# 05_Audio.net
KiCad netlist of a schematic drawn in Altium Designer
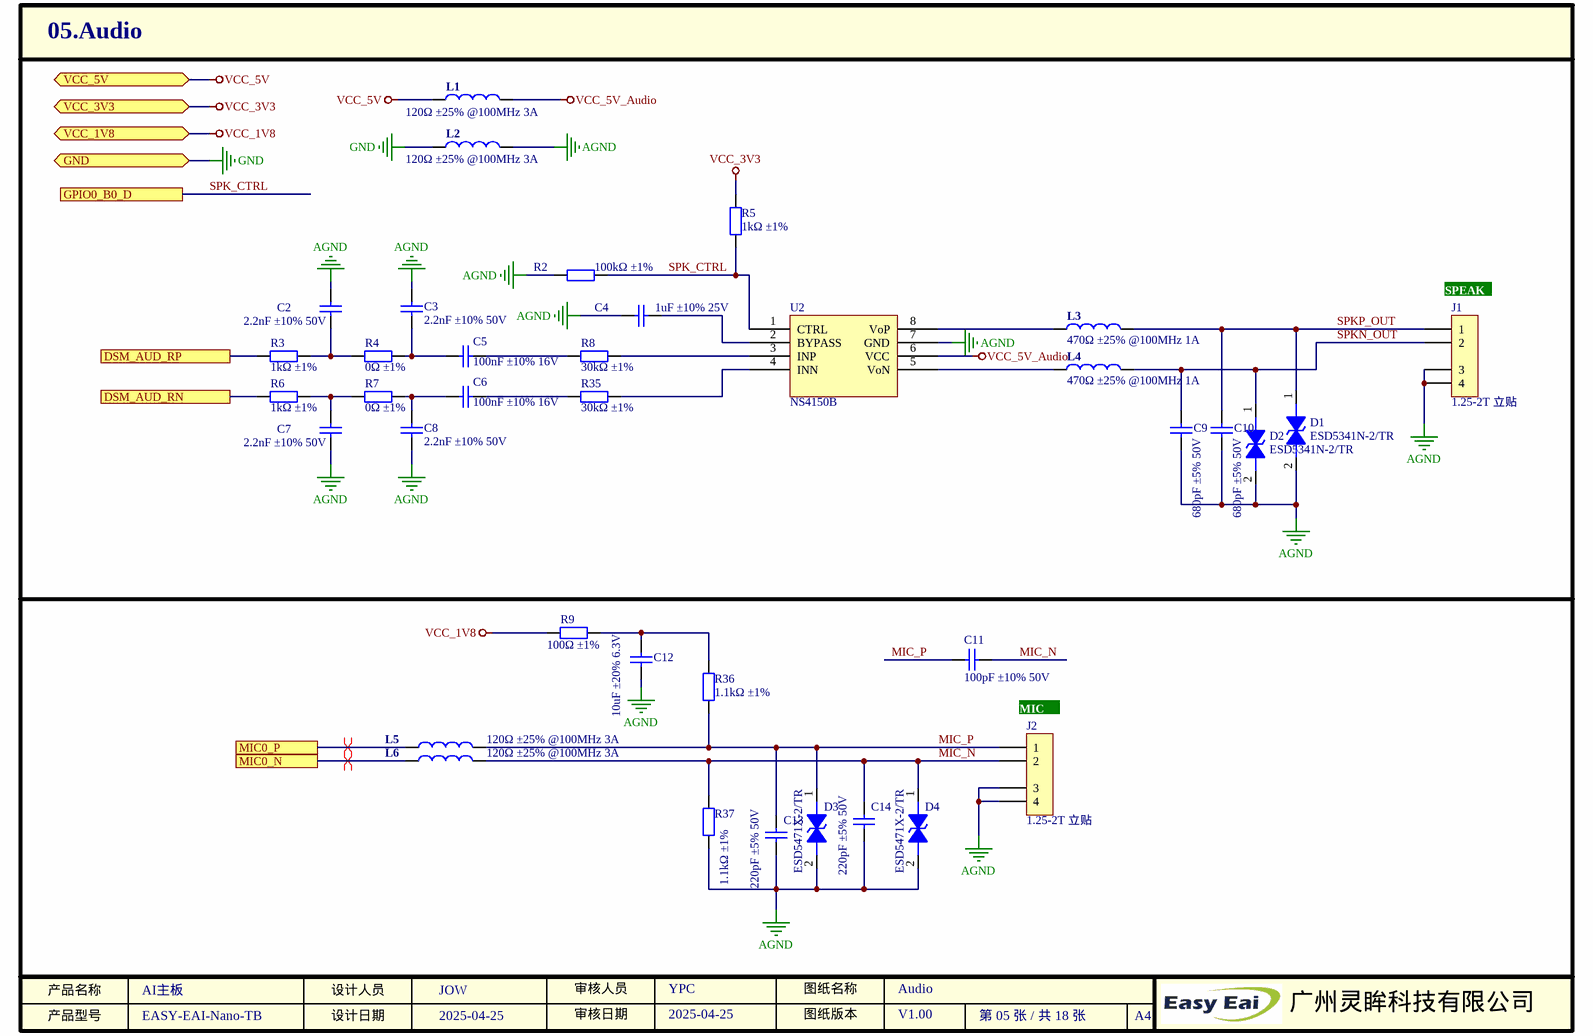
[diagram p0: 05.Audio.SchDoc]

(export (version "E")
  (design (tool "Eeschema 10.0.6"))
  (components
    (comp (ref "C2")
      (value "0402B222K500NT")
      (footprint "0402_C")
      (description "SPZL000399")
      (fields (field (name "描述") "2.2nF ±10% 50V"))
      (libsource (lib "CAP_EASY-EAI") (part "0402 2.2nF ±10% 50V"))
    )
    (comp (ref "C3")
      (value "0402B222K500NT")
      (footprint "0402_C")
      (description "SPZL000399")
      (fields (field (name "描述") "2.2nF ±10% 50V"))
      (libsource (lib "CAP_EASY-EAI") (part "0402 2.2nF ±10% 50V"))
    )
    (comp (ref "C4")
      (value "CL05A105KA5NQNC")
      (footprint "0402_C")
      (description "SPZL000337")
      (fields (field (name "描述") "1uF ±10% 25V"))
      (libsource (lib "CAP_EASY-EAI") (part "0402 1uF ±10% 25V"))
    )
    (comp (ref "C5")
      (value "CL05B104KO5NNNC")
      (footprint "0402_C")
      (description "SPZL000259")
      (fields (field (name "描述") "100nF ±10% 16V"))
      (libsource (lib "CAP_EASY-EAI") (part "0402 100nF ±10% 16V"))
    )
    (comp (ref "C6")
      (value "CL05B104KO5NNNC")
      (footprint "0402_C")
      (description "SPZL000259")
      (fields (field (name "描述") "100nF ±10% 16V"))
      (libsource (lib "CAP_EASY-EAI") (part "0402 100nF ±10% 16V"))
    )
    (comp (ref "C7")
      (value "0402B222K500NT")
      (footprint "0402_C")
      (description "SPZL000399")
      (fields (field (name "描述") "2.2nF ±10% 50V"))
      (libsource (lib "CAP_EASY-EAI") (part "0402 2.2nF ±10% 50V"))
    )
    (comp (ref "C8")
      (value "0402B222K500NT")
      (footprint "0402_C")
      (description "SPZL000399")
      (fields (field (name "描述") "2.2nF ±10% 50V"))
      (libsource (lib "CAP_EASY-EAI") (part "0402 2.2nF ±10% 50V"))
    )
    (comp (ref "C9")
      (value "CL05C681JB5NNNC")
      (footprint "0402_C")
      (description "SPZL000317")
      (fields (field (name "描述") "680pF ±5% 50V"))
      (libsource (lib "CAP_EASY-EAI") (part "0402 680pF ±5% 50V"))
    )
    (comp (ref "C10")
      (value "CL05C681JB5NNNC")
      (footprint "0402_C")
      (description "SPZL000317")
      (fields (field (name "描述") "680pF ±5% 50V"))
      (libsource (lib "CAP_EASY-EAI") (part "0402 680pF ±5% 50V"))
    )
    (comp (ref "C11")
      (value "CC0402KRX7R9BB101")
      (footprint "0402_C")
      (description "SPZL000312")
      (fields (field (name "描述") "100pF ±10% 50V"))
      (libsource (lib "CAP_EASY-EAI") (part "0402 100pF ±10% 50V"))
    )
    (comp (ref "C12")
      (value "CL05A106MQ5NUNC")
      (footprint "0402_C")
      (description "SPZL000269")
      (fields (field (name "描述") "10uF ±20% 6.3V"))
      (libsource (lib "CAP_lexing") (part "0402 10uF ±20% 6.3V"))
    )
    (comp (ref "C13")
      (value "GCM1555G1H221JA16D")
      (footprint "0402_C")
      (description "SPZL000318")
      (fields (field (name "描述") "220pF ±5% 50V"))
      (libsource (lib "CAP_lexing") (part "0402 220pF ±5% 50V"))
    )
    (comp (ref "C14")
      (value "GCM1555G1H221JA16D")
      (footprint "0402_C")
      (description "SPZL000318")
      (fields (field (name "描述") "220pF ±5% 50V"))
      (libsource (lib "CAP_lexing") (part "0402 220pF ±5% 50V"))
    )
    (comp (ref "D1")
      (value "ESD5341N-2/TR")
      (footprint "DFN1006-2L")
      (description "SPZL000253")
      (fields (field (name "型号") "ESD5341N-2/TR"))
      (libsource (lib "ESD_EASY-EAI") (part "TVS ESD5341N-2/TR"))
    )
    (comp (ref "D2")
      (value "ESD5341N-2/TR")
      (footprint "DFN1006-2L")
      (description "SPZL000253")
      (fields (field (name "型号") "ESD5341N-2/TR"))
      (libsource (lib "ESD_EASY-EAI") (part "TVS ESD5341N-2/TR"))
    )
    (comp (ref "D3")
      (value "ESD5471X-2/TR")
      (footprint "FBP-02C")
      (description "SPZL000254")
      (fields (field (name "型号") "ESD5471X-2/TR"))
      (libsource (lib "ESD_lexing") (part "TVS ESD5471X-2/TR"))
    )
    (comp (ref "D4")
      (value "ESD5471X-2/TR")
      (footprint "FBP-02C")
      (description "SPZL000254")
      (fields (field (name "型号") "ESD5471X-2/TR"))
      (libsource (lib "ESD_lexing") (part "TVS ESD5471X-2/TR"))
    )
    (comp (ref "J1")
      (value "AFC12-S02CCA-00")
      (footprint "1.25-2T_SMD_L")
      (description "SPZL000112")
      (fields (field (name "描述") "1.25-2T 立贴"))
      (libsource (lib "EVBoard-RK3562") (part "1.25-2T 立贴"))
    )
    (comp (ref "J2")
      (value "AFC12-S02CCA-00")
      (footprint "1.25-2T_SMD_L")
      (description "SPZL000112")
      (fields (field (name "描述") "1.25-2T 立贴"))
      (libsource (lib "EVBoard-RK3562") (part "1.25-2T 立贴"))
    )
    (comp (ref "L1")
      (value "BLM18KG121TN1D")
      (footprint "0603_R")
      (description "SPZL000842")
      (fields (field (name "描述") "120Ω ±25% @100MHz 3A"))
      (libsource (lib "Inductor_lexing") (part "120Ω ±25% @100MHz 3A"))
    )
    (comp (ref "L2")
      (value "BLM18KG121TN1D")
      (footprint "0603_R")
      (description "SPZL000842")
      (fields (field (name "描述") "120Ω ±25% @100MHz 3A"))
      (libsource (lib "Inductor_lexing") (part "120Ω ±25% @100MHz 3A"))
    )
    (comp (ref "L3")
      (value "PZ1608U471-1R0TF")
      (footprint "0603_R")
      (description "SPZL000054")
      (fields (field (name "描述") "470Ω ±25% @100MHz 1A"))
      (libsource (lib "Inductor_EASY-EAI") (part "470Ω ±25% @100MHz 1A"))
    )
    (comp (ref "L4")
      (value "PZ1608U471-1R0TF")
      (footprint "0603_R")
      (description "SPZL000054")
      (fields (field (name "描述") "470Ω ±25% @100MHz 1A"))
      (libsource (lib "Inductor_EASY-EAI") (part "470Ω ±25% @100MHz 1A"))
    )
    (comp (ref "L5")
      (value "BLM18KG121TN1D")
      (footprint "0603_R")
      (description "SPZL000842")
      (fields (field (name "描述") "120Ω ±25% @100MHz 3A"))
      (libsource (lib "Inductor_lexing") (part "120Ω ±25% @100MHz 3A"))
    )
    (comp (ref "L6")
      (value "BLM18KG121TN1D")
      (footprint "0603_R")
      (description "SPZL000842")
      (fields (field (name "描述") "120Ω ±25% @100MHz 3A"))
      (libsource (lib "Inductor_lexing") (part "120Ω ±25% @100MHz 3A"))
    )
    (comp (ref "R2")
      (value "0402WGF1003TCE")
      (footprint "0402_R")
      (description "SPZL000282")
      (fields (field (name "描述") "100kΩ ±1%"))
      (libsource (lib "RES_EASY-EAI") (part "0402 100kΩ ±1%"))
    )
    (comp (ref "R3")
      (value "0402WGF1001TCE")
      (footprint "0402_R")
      (description "SPZL000275")
      (fields (field (name "描述") "1kΩ ±1%"))
      (libsource (lib "RES_EASY-EAI") (part "0402 1kΩ ±1%"))
    )
    (comp (ref "R4")
      (value "0402WGF0000TCE")
      (footprint "0402_R")
      (description "SPZL000276")
      (fields (field (name "描述") "0Ω ±1%"))
      (libsource (lib "RES_EASY-EAI") (part "0402 0Ω ±1%"))
    )
    (comp (ref "R5")
      (value "0402WGF1001TCE")
      (footprint "0402_R")
      (description "SPZL000275")
      (fields (field (name "描述") "1kΩ ±1%"))
      (libsource (lib "") (part "0402 1kΩ ±1%_1"))
    )
    (comp (ref "R6")
      (value "0402WGF1001TCE")
      (footprint "0402_R")
      (description "SPZL000275")
      (fields (field (name "描述") "1kΩ ±1%"))
      (libsource (lib "RES_EASY-EAI") (part "0402 1kΩ ±1%"))
    )
    (comp (ref "R7")
      (value "0402WGF0000TCE")
      (footprint "0402_R")
      (description "SPZL000276")
      (fields (field (name "描述") "0Ω ±1%"))
      (libsource (lib "RES_EASY-EAI") (part "0402 0Ω ±1%"))
    )
    (comp (ref "R8")
      (value "NQ02WGF3002TCE")
      (footprint "0402_R")
      (description "SPZL000323")
      (fields (field (name "描述") "30kΩ ±1%"))
      (libsource (lib "RES_EASY-EAI") (part "0402 30kΩ ±1%"))
    )
    (comp (ref "R9")
      (value "0402WGF1000TCE")
      (footprint "0402_R")
      (description "SPZL000281")
      (fields (field (name "描述") "100Ω ±1%"))
      (libsource (lib "RES_lexing") (part "0402 100Ω ±1%"))
    )
    (comp (ref "R35")
      (value "NQ02WGF3002TCE")
      (footprint "0402_R")
      (description "SPZL000323")
      (fields (field (name "描述") "30kΩ ±1%"))
      (libsource (lib "RES_EASY-EAI") (part "0402 30kΩ ±1%"))
    )
    (comp (ref "R36")
      (value "AC0402FR-071K1L")
      (footprint "0402_R")
      (description "SPZL000324")
      (fields (field (name "描述") "1.1kΩ ±1%"))
      (libsource (lib "RES_EASY-EAI") (part "0402 1.1kΩ ±1%"))
    )
    (comp (ref "R37")
      (value "AC0402FR-071K1L")
      (footprint "0402_R")
      (description "SPZL000324")
      (fields (field (name "描述") "1.1kΩ ±1%"))
      (libsource (lib "RES_EASY-EAI") (part "0402 1.1kΩ ±1%"))
    )
    (comp (ref "U2")
      (value "NS4150B")
      (footprint "MSOP-8")
      (description "SPZL000086")
      (fields (field (name "型号") "NS4150B"))
      (libsource (lib "IC_EASY-EAI") (part "NS4150B"))
    )
  )
  (nets
    (net (code "1") (name "/DSM_AUD_RN") (class "Default")
      (node (ref "R6") (pin "1") (pinfunction "1_1") (pintype "passive"))
    )
    (net (code "2") (name "/DSM_AUD_RP") (class "Default")
      (node (ref "R3") (pin "1") (pinfunction "1_1") (pintype "passive"))
    )
    (net (code "3") (name "/MIC0_N") (class "Default")
      (node (ref "L6") (pin "1") (pinfunction "1_1") (pintype "passive"))
    )
    (net (code "4") (name "/MIC0_P") (class "Default")
      (node (ref "L5") (pin "1") (pinfunction "1_1") (pintype "passive"))
    )
    (net (code "5") (name "/MIC_N") (class "Default")
      (node (ref "C11") (pin "2") (pinfunction "2_2") (pintype "passive"))
      (node (ref "C14") (pin "2") (pinfunction "2_2") (pintype "passive"))
      (node (ref "D4") (pin "1") (pinfunction "1_1") (pintype "passive"))
      (node (ref "J2") (pin "2") (pinfunction "2_2") (pintype "passive"))
      (node (ref "L6") (pin "2") (pinfunction "2_2") (pintype "passive"))
      (node (ref "R37") (pin "2") (pinfunction "2_2") (pintype "passive"))
    )
    (net (code "6") (name "/MIC_P") (class "Default")
      (node (ref "C11") (pin "1") (pinfunction "1_1") (pintype "passive"))
      (node (ref "C13") (pin "2") (pinfunction "2_2") (pintype "passive"))
      (node (ref "D3") (pin "1") (pinfunction "1_1") (pintype "passive"))
      (node (ref "J2") (pin "1") (pinfunction "1_1") (pintype "passive"))
      (node (ref "L5") (pin "2") (pinfunction "2_2") (pintype "passive"))
      (node (ref "R36") (pin "1") (pinfunction "1_1") (pintype "passive"))
    )
    (net (code "7") (name "/SPKN_OUT") (class "Default")
      (node (ref "C9") (pin "2") (pinfunction "2_2") (pintype "passive"))
      (node (ref "D2") (pin "1") (pinfunction "1_1") (pintype "passive"))
      (node (ref "J1") (pin "2") (pinfunction "2_2") (pintype "passive"))
      (node (ref "L4") (pin "2") (pinfunction "2_2") (pintype "passive"))
    )
    (net (code "8") (name "/SPKP_OUT") (class "Default")
      (node (ref "C10") (pin "2") (pinfunction "2_2") (pintype "passive"))
      (node (ref "D1") (pin "1") (pinfunction "1_1") (pintype "passive"))
      (node (ref "J1") (pin "1") (pinfunction "1_1") (pintype "passive"))
      (node (ref "L3") (pin "2") (pinfunction "2_2") (pintype "passive"))
    )
    (net (code "9") (name "/SPK_CTRL") (class "Default")
      (node (ref "R2") (pin "2") (pinfunction "2_2") (pintype "passive"))
      (node (ref "R5") (pin "1") (pinfunction "1_1") (pintype "passive"))
      (node (ref "U2") (pin "1") (pinfunction "CTRL_1") (pintype "passive"))
    )
    (net (code "10") (name "AGND") (class "Default")
      (node (ref "C10") (pin "1") (pinfunction "1_1") (pintype "passive"))
      (node (ref "C12") (pin "1") (pinfunction "1_1") (pintype "passive"))
      (node (ref "C13") (pin "1") (pinfunction "1_1") (pintype "passive"))
      (node (ref "C14") (pin "1") (pinfunction "1_1") (pintype "passive"))
      (node (ref "C2") (pin "2") (pinfunction "2_2") (pintype "passive"))
      (node (ref "C3") (pin "2") (pinfunction "2_2") (pintype "passive"))
      (node (ref "C4") (pin "1") (pinfunction "1_1") (pintype "passive"))
      (node (ref "C7") (pin "1") (pinfunction "1_1") (pintype "passive"))
      (node (ref "C8") (pin "1") (pinfunction "1_1") (pintype "passive"))
      (node (ref "C9") (pin "1") (pinfunction "1_1") (pintype "passive"))
      (node (ref "D1") (pin "2") (pinfunction "2_2") (pintype "passive"))
      (node (ref "D2") (pin "2") (pinfunction "2_2") (pintype "passive"))
      (node (ref "D3") (pin "2") (pinfunction "2_2") (pintype "passive"))
      (node (ref "D4") (pin "2") (pinfunction "2_2") (pintype "passive"))
      (node (ref "J1") (pin "3") (pinfunction "3_3") (pintype "passive"))
      (node (ref "J1") (pin "4") (pinfunction "4_4") (pintype "passive"))
      (node (ref "J2") (pin "3") (pinfunction "3_3") (pintype "passive"))
      (node (ref "J2") (pin "4") (pinfunction "4_4") (pintype "passive"))
      (node (ref "L2") (pin "2") (pinfunction "2_2") (pintype "passive"))
      (node (ref "R2") (pin "1") (pinfunction "1_1") (pintype "passive"))
      (node (ref "R37") (pin "1") (pinfunction "1_1") (pintype "passive"))
      (node (ref "U2") (pin "7") (pinfunction "GND_7") (pintype "passive"))
    )
    (net (code "11") (name "GND") (class "Default")
      (node (ref "L2") (pin "1") (pinfunction "1_1") (pintype "passive"))
    )
    (net (code "12") (name "Net-(C2-Pad1)") (class "Default")
      (node (ref "C2") (pin "1") (pinfunction "1_1") (pintype "passive"))
      (node (ref "R3") (pin "2") (pinfunction "2_2") (pintype "passive"))
      (node (ref "R4") (pin "1") (pinfunction "1_1") (pintype "passive"))
    )
    (net (code "13") (name "Net-(C3-Pad1)") (class "Default")
      (node (ref "C3") (pin "1") (pinfunction "1_1") (pintype "passive"))
      (node (ref "C5") (pin "1") (pinfunction "1_1") (pintype "passive"))
      (node (ref "R4") (pin "2") (pinfunction "2_2") (pintype "passive"))
    )
    (net (code "14") (name "Net-(C5-Pad2)") (class "Default")
      (node (ref "C5") (pin "2") (pinfunction "2_2") (pintype "passive"))
      (node (ref "R8") (pin "1") (pinfunction "1_1") (pintype "passive"))
    )
    (net (code "15") (name "Net-(C6-Pad1)") (class "Default")
      (node (ref "C6") (pin "1") (pinfunction "1_1") (pintype "passive"))
      (node (ref "C8") (pin "2") (pinfunction "2_2") (pintype "passive"))
      (node (ref "R7") (pin "2") (pinfunction "2_2") (pintype "passive"))
    )
    (net (code "16") (name "Net-(C6-Pad2)") (class "Default")
      (node (ref "C6") (pin "2") (pinfunction "2_2") (pintype "passive"))
      (node (ref "R35") (pin "1") (pinfunction "1_1") (pintype "passive"))
    )
    (net (code "17") (name "Net-(C7-Pad2)") (class "Default")
      (node (ref "C7") (pin "2") (pinfunction "2_2") (pintype "passive"))
      (node (ref "R6") (pin "2") (pinfunction "2_2") (pintype "passive"))
      (node (ref "R7") (pin "1") (pinfunction "1_1") (pintype "passive"))
    )
    (net (code "18") (name "Net-(C12-Pad2)") (class "Default")
      (node (ref "C12") (pin "2") (pinfunction "2_2") (pintype "passive"))
      (node (ref "R36") (pin "2") (pinfunction "2_2") (pintype "passive"))
      (node (ref "R9") (pin "2") (pinfunction "2_2") (pintype "passive"))
    )
    (net (code "19") (name "Net-(U2-BYPASS)") (class "Default")
      (node (ref "C4") (pin "2") (pinfunction "2_2") (pintype "passive"))
      (node (ref "U2") (pin "2") (pinfunction "BYPASS_2") (pintype "passive"))
    )
    (net (code "20") (name "Net-(U2-INN)") (class "Default")
      (node (ref "R35") (pin "2") (pinfunction "2_2") (pintype "passive"))
      (node (ref "U2") (pin "4") (pinfunction "INN_4") (pintype "passive"))
    )
    (net (code "21") (name "Net-(U2-INP)") (class "Default")
      (node (ref "R8") (pin "2") (pinfunction "2_2") (pintype "passive"))
      (node (ref "U2") (pin "3") (pinfunction "INP_3") (pintype "passive"))
    )
    (net (code "22") (name "Net-(U2-VoN)") (class "Default")
      (node (ref "L4") (pin "1") (pinfunction "1_1") (pintype "passive"))
      (node (ref "U2") (pin "5") (pinfunction "VoN_5") (pintype "passive"))
    )
    (net (code "23") (name "Net-(U2-VoP)") (class "Default")
      (node (ref "L3") (pin "1") (pinfunction "1_1") (pintype "passive"))
      (node (ref "U2") (pin "8") (pinfunction "VoP_8") (pintype "passive"))
    )
    (net (code "24") (name "VCC_1V8") (class "Default")
      (node (ref "R9") (pin "1") (pinfunction "1_1") (pintype "passive"))
    )
    (net (code "25") (name "VCC_3V3") (class "Default")
      (node (ref "R5") (pin "2") (pinfunction "2_2") (pintype "passive"))
    )
    (net (code "26") (name "VCC_5V") (class "Default")
      (node (ref "L1") (pin "1") (pinfunction "1_1") (pintype "passive"))
    )
    (net (code "27") (name "VCC_5V_Audio") (class "Default")
      (node (ref "L1") (pin "2") (pinfunction "2_2") (pintype "passive"))
      (node (ref "U2") (pin "6") (pinfunction "VCC_6") (pintype "passive"))
    )
  )
)
